# dcdc12v.net
KiCad netlist of a schematic drawn in Altium Designer
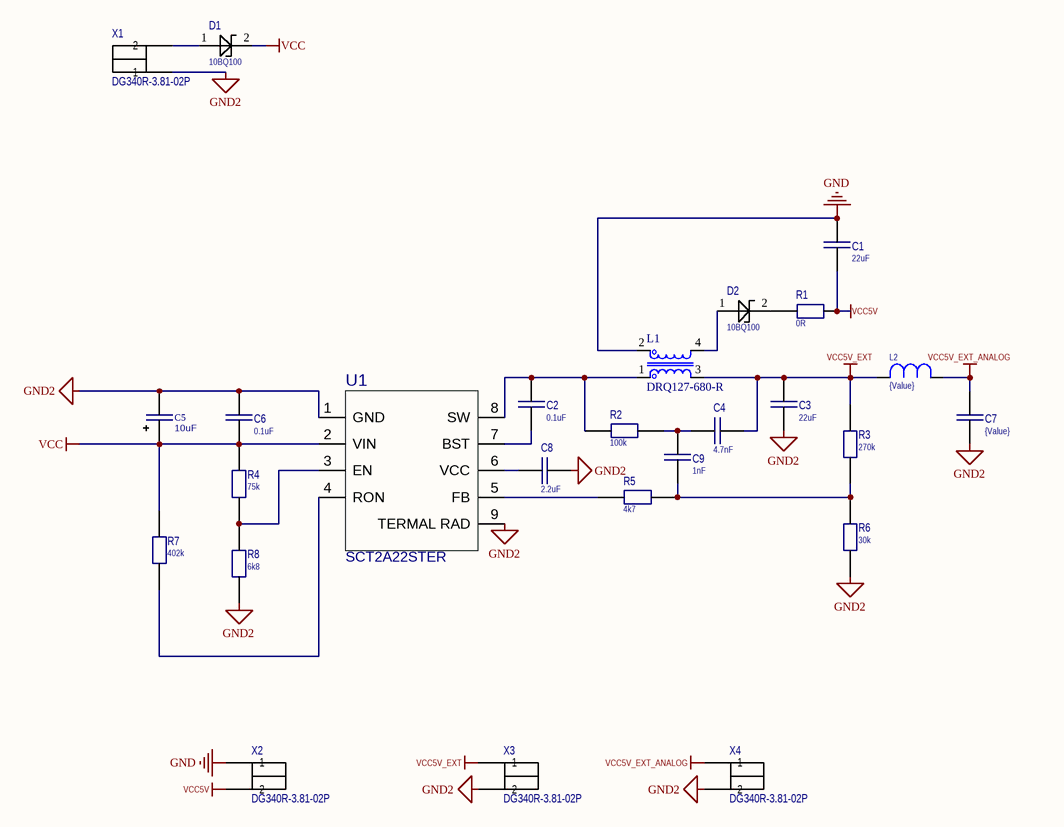
[diagram p0: dcdc12v.SchDoc]

(export (version "E")
  (design (tool "Eeschema 10.0.6"))
  (components
    (comp (ref "C1")
      (value "22uF")
      (footprint "C_0603")
      (description "Capacitor")
      (fields
        (field (name "PART NUMBER") "CC0603MRX5R6BB226")
        (field (name "ALTERNATIVE PART") "CC0603MRX6S5BB226")
      )
      (libsource (lib "capacitors") (part "C0603"))
    )
    (comp (ref "C2")
      (value "0.1uF")
      (footprint "C_0603")
      (description "Capacitor")
      (fields
        (field (name "PART NUMBER") "CC0603KRX7R9BB104")
        (field (name "ALTERNATIVE PART") "CC0603MRY5V9BB104")
      )
      (libsource (lib "capacitors") (part "C0603"))
    )
    (comp (ref "C3")
      (value "22uF")
      (footprint "C_0603")
      (description "Capacitor")
      (fields
        (field (name "PART NUMBER") "CC0603MRX5R6BB226")
        (field (name "ALTERNATIVE PART") "CC0603MRX6S5BB226")
      )
      (libsource (lib "capacitors") (part "C0603"))
    )
    (comp (ref "C4")
      (value "4.7nF")
      (footprint "C_0603")
      (description "Capacitor")
      (fields
        (field (name "PART NUMBER") "CC0603KRX7R9BB472")
        (field (name "ALTERNATIVE PART") "CC0603JRX7R9BB472")
      )
      (libsource (lib "capacitors") (part "C0603"))
    )
    (comp (ref "C5")
      (value "10uF")
      (footprint "CAP470X25V")
      (description "Capacitor")
      (fields (field (name "PART NUMBER") "SH160M0010B5S-1012"))
      (libsource (lib "capacitors") (part "C_10_12_5mm"))
    )
    (comp (ref "C6")
      (value "0.1uF")
      (footprint "C_1206")
      (description "Capacitor")
      (fields
        (field (name "PART NUMBER") "CC1206KKX7R0BB104")
        (field (name "ALTERNATIVE PART") "CC1206JKX7R0BB104")
      )
      (libsource (lib "capacitors") (part "C1206"))
    )
    (comp (ref "C7")
      (value "{Value}")
      (footprint "C_0603")
      (description "Capacitor")
      (libsource (lib "capacitors") (part "C0603"))
    )
    (comp (ref "C8")
      (value "2.2uF")
      (footprint "C_0603")
      (description "Capacitor")
      (fields (field (name "PART NUMBER") "CC0603KRX5R8BB225"))
      (libsource (lib "capacitors") (part "C0603"))
    )
    (comp (ref "C9")
      (value "1nF")
      (footprint "C_0603")
      (description "Capacitor")
      (fields
        (field (name "PART NUMBER") "CC0603KRX7R9BB102")
        (field (name "ALTERNATIVE PART") "CC0603KRX7R8BB102")
      )
      (libsource (lib "capacitors") (part "C0603"))
    )
    (comp (ref "D1")
      (value "10BQ100")
      (footprint "DO-214AA")
      (description "Diode")
      (fields (field (name "ALTERNATIVE PART") "VS-10BQ100"))
      (libsource (lib "diode") (part "D_DO-214AA"))
    )
    (comp (ref "D2")
      (value "10BQ100")
      (footprint "DO-214AA")
      (description "Diode")
      (fields (field (name "ALTERNATIVE PART") "VS-10BQ100"))
      (libsource (lib "diode") (part "D_DO-214AA"))
    )
    (comp (ref "L1")
      (value "DRQ127-680-R")
      (footprint "inductors_transformers:XFMR_DRQ127-150-R")
      (description "Inductor Power Shielded")
      (libsource (lib "inductors_transformers") (part "DRQ127-150-R"))
    )
    (comp (ref "L2")
      (value "{Value}")
      (footprint "CD54NP")
      (description "Inductor")
      (libsource (lib "inductors_transformers") (part "L_CD54NP"))
    )
    (comp (ref "R1")
      (value "0R")
      (footprint "R_0603")
      (description "Resistor")
      (fields
        (field (name "PART NUMBER") "RC0603JR-070RL")
        (field (name "ALTERNATIVE PART") "RC0603JR-100RL")
      )
      (libsource (lib "resistors") (part "R0603"))
    )
    (comp (ref "R2")
      (value "100k")
      (footprint "R_0603")
      (description "Resistor")
      (fields
        (field (name "PART NUMBER") "RC0603FR-07100KL")
        (field (name "ALTERNATIVE PART") "RC0603JR-07100KL")
      )
      (libsource (lib "resistors") (part "R0603"))
    )
    (comp (ref "R3")
      (value "270k")
      (footprint "R_0603")
      (description "Resistor")
      (fields
        (field (name "PART NUMBER") "RC0603FR-07270KL")
        (field (name "ALTERNATIVE PART") "RC0603JR-07270KL")
      )
      (libsource (lib "resistors") (part "R0603"))
    )
    (comp (ref "R4")
      (value "75k")
      (footprint "R_0603")
      (description "Resistor")
      (fields
        (field (name "PART NUMBER") "RC0603JR-0775KL")
        (field (name "ALTERNATIVE PART") "RC0603FR-0775KL")
      )
      (libsource (lib "resistors") (part "R0603"))
    )
    (comp (ref "R5")
      (value "4k7")
      (footprint "R_0603")
      (description "Resistor")
      (fields
        (field (name "PART NUMBER") "RC0603FR-074K7L")
        (field (name "ALTERNATIVE PART") "RC0603JR-074K7L")
      )
      (libsource (lib "resistors") (part "R0603"))
    )
    (comp (ref "R6")
      (value "30k")
      (footprint "R_0603")
      (description "Resistor")
      (fields
        (field (name "PART NUMBER") "RC0603FR-0730KL")
        (field (name "ALTERNATIVE PART") "RC0603JR-0730KL")
      )
      (libsource (lib "resistors") (part "R0603"))
    )
    (comp (ref "R7")
      (value "402k")
      (footprint "R_0603")
      (description "Resistor")
      (fields
        (field (name "PART NUMBER") "RC0603FR-07402KL")
        (field (name "ALTERNATIVE PART") "RC0603FR-13402KL")
      )
      (libsource (lib "resistors") (part "R0603"))
    )
    (comp (ref "R8")
      (value "6k8")
      (footprint "R_0603")
      (description "Resistor")
      (fields
        (field (name "PART NUMBER") "RC0603FR-076K8L")
        (field (name "ALTERNATIVE PART") "RC0603JR-076K8L")
      )
      (libsource (lib "resistors") (part "R0603"))
    )
    (comp (ref "U1")
      (value "SCT2A22STER")
      (footprint "ESOP-8")
      (description "Buck dc/dc")
      (libsource (lib "dcdc_ldo_ref") (part "SCT2A22STER"))
    )
    (comp (ref "X1")
      (value "DG340R-3.81-02P")
      (footprint "340-021-12")
      (description "Connectors")
      (fields
        (field (name "TYPE") "DG340R-3.81-02P")
        (field (name "ALTERNATIVE PART") "KLS2-340-3.81-02P-2S")
      )
      (libsource (lib "connectors_socets") (part "DG340R-3.81-02P"))
    )
    (comp (ref "X2")
      (value "DG340R-3.81-02P")
      (footprint "340-021-12")
      (description "Connectors")
      (fields
        (field (name "TYPE") "DG340R-3.81-02P")
        (field (name "ALTERNATIVE PART") "KLS2-340-3.81-02P-2S")
      )
      (libsource (lib "connectors_socets") (part "DG340R-3.81-02P"))
    )
    (comp (ref "X3")
      (value "DG340R-3.81-02P")
      (footprint "340-021-12")
      (description "Connectors")
      (fields
        (field (name "TYPE") "DG340R-3.81-02P")
        (field (name "ALTERNATIVE PART") "KLS2-340-3.81-02P-2S")
      )
      (libsource (lib "connectors_socets") (part "DG340R-3.81-02P"))
    )
    (comp (ref "X4")
      (value "DG340R-3.81-02P")
      (footprint "340-021-12")
      (description "Connectors")
      (fields
        (field (name "TYPE") "DG340R-3.81-02P")
        (field (name "ALTERNATIVE PART") "KLS2-340-3.81-02P-2S")
      )
      (libsource (lib "connectors_socets") (part "DG340R-3.81-02P"))
    )
  )
  (nets
    (net (code "1") (name "GND") (class "Default")
      (node (ref "C1") (pin "2") (pinfunction "2_2") (pintype "passive"))
      (node (ref "L1") (pin "2") (pinfunction "2_2") (pintype "passive"))
      (node (ref "X2") (pin "1") (pinfunction "1_1") (pintype "passive"))
    )
    (net (code "2") (name "GND2") (class "Default")
      (node (ref "C3") (pin "1") (pinfunction "1_1") (pintype "passive"))
      (node (ref "C5") (pin "1") (pinfunction "1_1") (pintype "passive"))
      (node (ref "C6") (pin "2") (pinfunction "2_2") (pintype "passive"))
      (node (ref "C7") (pin "1") (pinfunction "1_1") (pintype "passive"))
      (node (ref "C8") (pin "1") (pinfunction "1_1") (pintype "passive"))
      (node (ref "R6") (pin "1") (pinfunction "1_1") (pintype "passive"))
      (node (ref "R8") (pin "1") (pinfunction "1_1") (pintype "passive"))
      (node (ref "U1") (pin "1") (pinfunction "GND_1") (pintype "passive"))
      (node (ref "U1") (pin "9") (pinfunction "TERMAL_RAD_9") (pintype "passive"))
      (node (ref "X1") (pin "1") (pinfunction "1_1") (pintype "passive"))
      (node (ref "X3") (pin "2") (pinfunction "2_2") (pintype "passive"))
      (node (ref "X4") (pin "2") (pinfunction "2_2") (pintype "passive"))
    )
    (net (code "3") (name "Net-(C4-Pad1)") (class "Default")
      (node (ref "C4") (pin "1") (pinfunction "1_1") (pintype "passive"))
      (node (ref "C9") (pin "1") (pinfunction "1_1") (pintype "passive"))
      (node (ref "R2") (pin "1") (pinfunction "1_1") (pintype "passive"))
    )
    (net (code "4") (name "Net-(C9-Pad2)") (class "Default")
      (node (ref "C9") (pin "2") (pinfunction "2_2") (pintype "passive"))
      (node (ref "R3") (pin "1") (pinfunction "1_1") (pintype "passive"))
      (node (ref "R5") (pin "2") (pinfunction "2_2") (pintype "passive"))
      (node (ref "R6") (pin "2") (pinfunction "2_2") (pintype "passive"))
    )
    (net (code "5") (name "Net-(D1-A)") (class "Default")
      (node (ref "D1") (pin "1") (pinfunction "A_1") (pintype "passive"))
      (node (ref "X1") (pin "2") (pinfunction "2_2") (pintype "passive"))
    )
    (net (code "6") (name "Net-(D2-A)") (class "Default")
      (node (ref "D2") (pin "1") (pinfunction "A_1") (pintype "passive"))
      (node (ref "L1") (pin "4") (pinfunction "4_4") (pintype "passive"))
    )
    (net (code "7") (name "Net-(D2-K)") (class "Default")
      (node (ref "D2") (pin "2") (pinfunction "K_2") (pintype "passive"))
      (node (ref "R1") (pin "2") (pinfunction "2_2") (pintype "passive"))
    )
    (net (code "8") (name "Net-(U1-BST)") (class "Default")
      (node (ref "C2") (pin "1") (pinfunction "1_1") (pintype "passive"))
      (node (ref "U1") (pin "7") (pinfunction "BST_7") (pintype "passive"))
    )
    (net (code "9") (name "Net-(U1-EN)") (class "Default")
      (node (ref "R4") (pin "1") (pinfunction "1_1") (pintype "passive"))
      (node (ref "R8") (pin "2") (pinfunction "2_2") (pintype "passive"))
      (node (ref "U1") (pin "3") (pinfunction "EN_3") (pintype "passive"))
    )
    (net (code "10") (name "Net-(U1-FB)") (class "Default")
      (node (ref "R5") (pin "1") (pinfunction "1_1") (pintype "passive"))
      (node (ref "U1") (pin "5") (pinfunction "FB_5") (pintype "passive"))
    )
    (net (code "11") (name "Net-(U1-RON)") (class "Default")
      (node (ref "R7") (pin "1") (pinfunction "1_1") (pintype "passive"))
      (node (ref "U1") (pin "4") (pinfunction "RON_4") (pintype "passive"))
    )
    (net (code "12") (name "Net-(U1-SW)") (class "Default")
      (node (ref "C2") (pin "2") (pinfunction "2_2") (pintype "passive"))
      (node (ref "L1") (pin "1") (pinfunction "1_1") (pintype "passive"))
      (node (ref "R2") (pin "2") (pinfunction "2_2") (pintype "passive"))
      (node (ref "U1") (pin "8") (pinfunction "SW_8") (pintype "passive"))
    )
    (net (code "13") (name "Net-(U1-VCC)") (class "Default")
      (node (ref "C8") (pin "2") (pinfunction "2_2") (pintype "passive"))
      (node (ref "U1") (pin "6") (pinfunction "VCC_6") (pintype "passive"))
    )
    (net (code "14") (name "VCC") (class "Default")
      (node (ref "C5") (pin "2") (pinfunction "2_2") (pintype "passive"))
      (node (ref "C6") (pin "1") (pinfunction "1_1") (pintype "passive"))
      (node (ref "D1") (pin "2") (pinfunction "K_2") (pintype "passive"))
      (node (ref "R4") (pin "2") (pinfunction "2_2") (pintype "passive"))
      (node (ref "R7") (pin "2") (pinfunction "2_2") (pintype "passive"))
      (node (ref "U1") (pin "2") (pinfunction "VIN_2") (pintype "passive"))
    )
    (net (code "15") (name "VCC5V") (class "Default")
      (node (ref "C1") (pin "1") (pinfunction "1_1") (pintype "passive"))
      (node (ref "R1") (pin "1") (pinfunction "1_1") (pintype "passive"))
      (node (ref "X2") (pin "2") (pinfunction "2_2") (pintype "passive"))
    )
    (net (code "16") (name "VCC5V_EXT") (class "Default")
      (node (ref "C3") (pin "2") (pinfunction "2_2") (pintype "passive"))
      (node (ref "C4") (pin "2") (pinfunction "2_2") (pintype "passive"))
      (node (ref "L1") (pin "3") (pinfunction "3_3") (pintype "passive"))
      (node (ref "L2") (pin "2") (pintype "passive"))
      (node (ref "R3") (pin "2") (pinfunction "2_2") (pintype "passive"))
      (node (ref "X3") (pin "1") (pinfunction "1_1") (pintype "passive"))
    )
    (net (code "17") (name "VCC5V_EXT_ANALOG") (class "Default")
      (node (ref "C7") (pin "2") (pinfunction "2_2") (pintype "passive"))
      (node (ref "L2") (pin "1") (pintype "passive"))
      (node (ref "X4") (pin "1") (pinfunction "1_1") (pintype "passive"))
    )
  )
)
